# design.net
KiCad netlist of a schematic drawn in Altium Designer
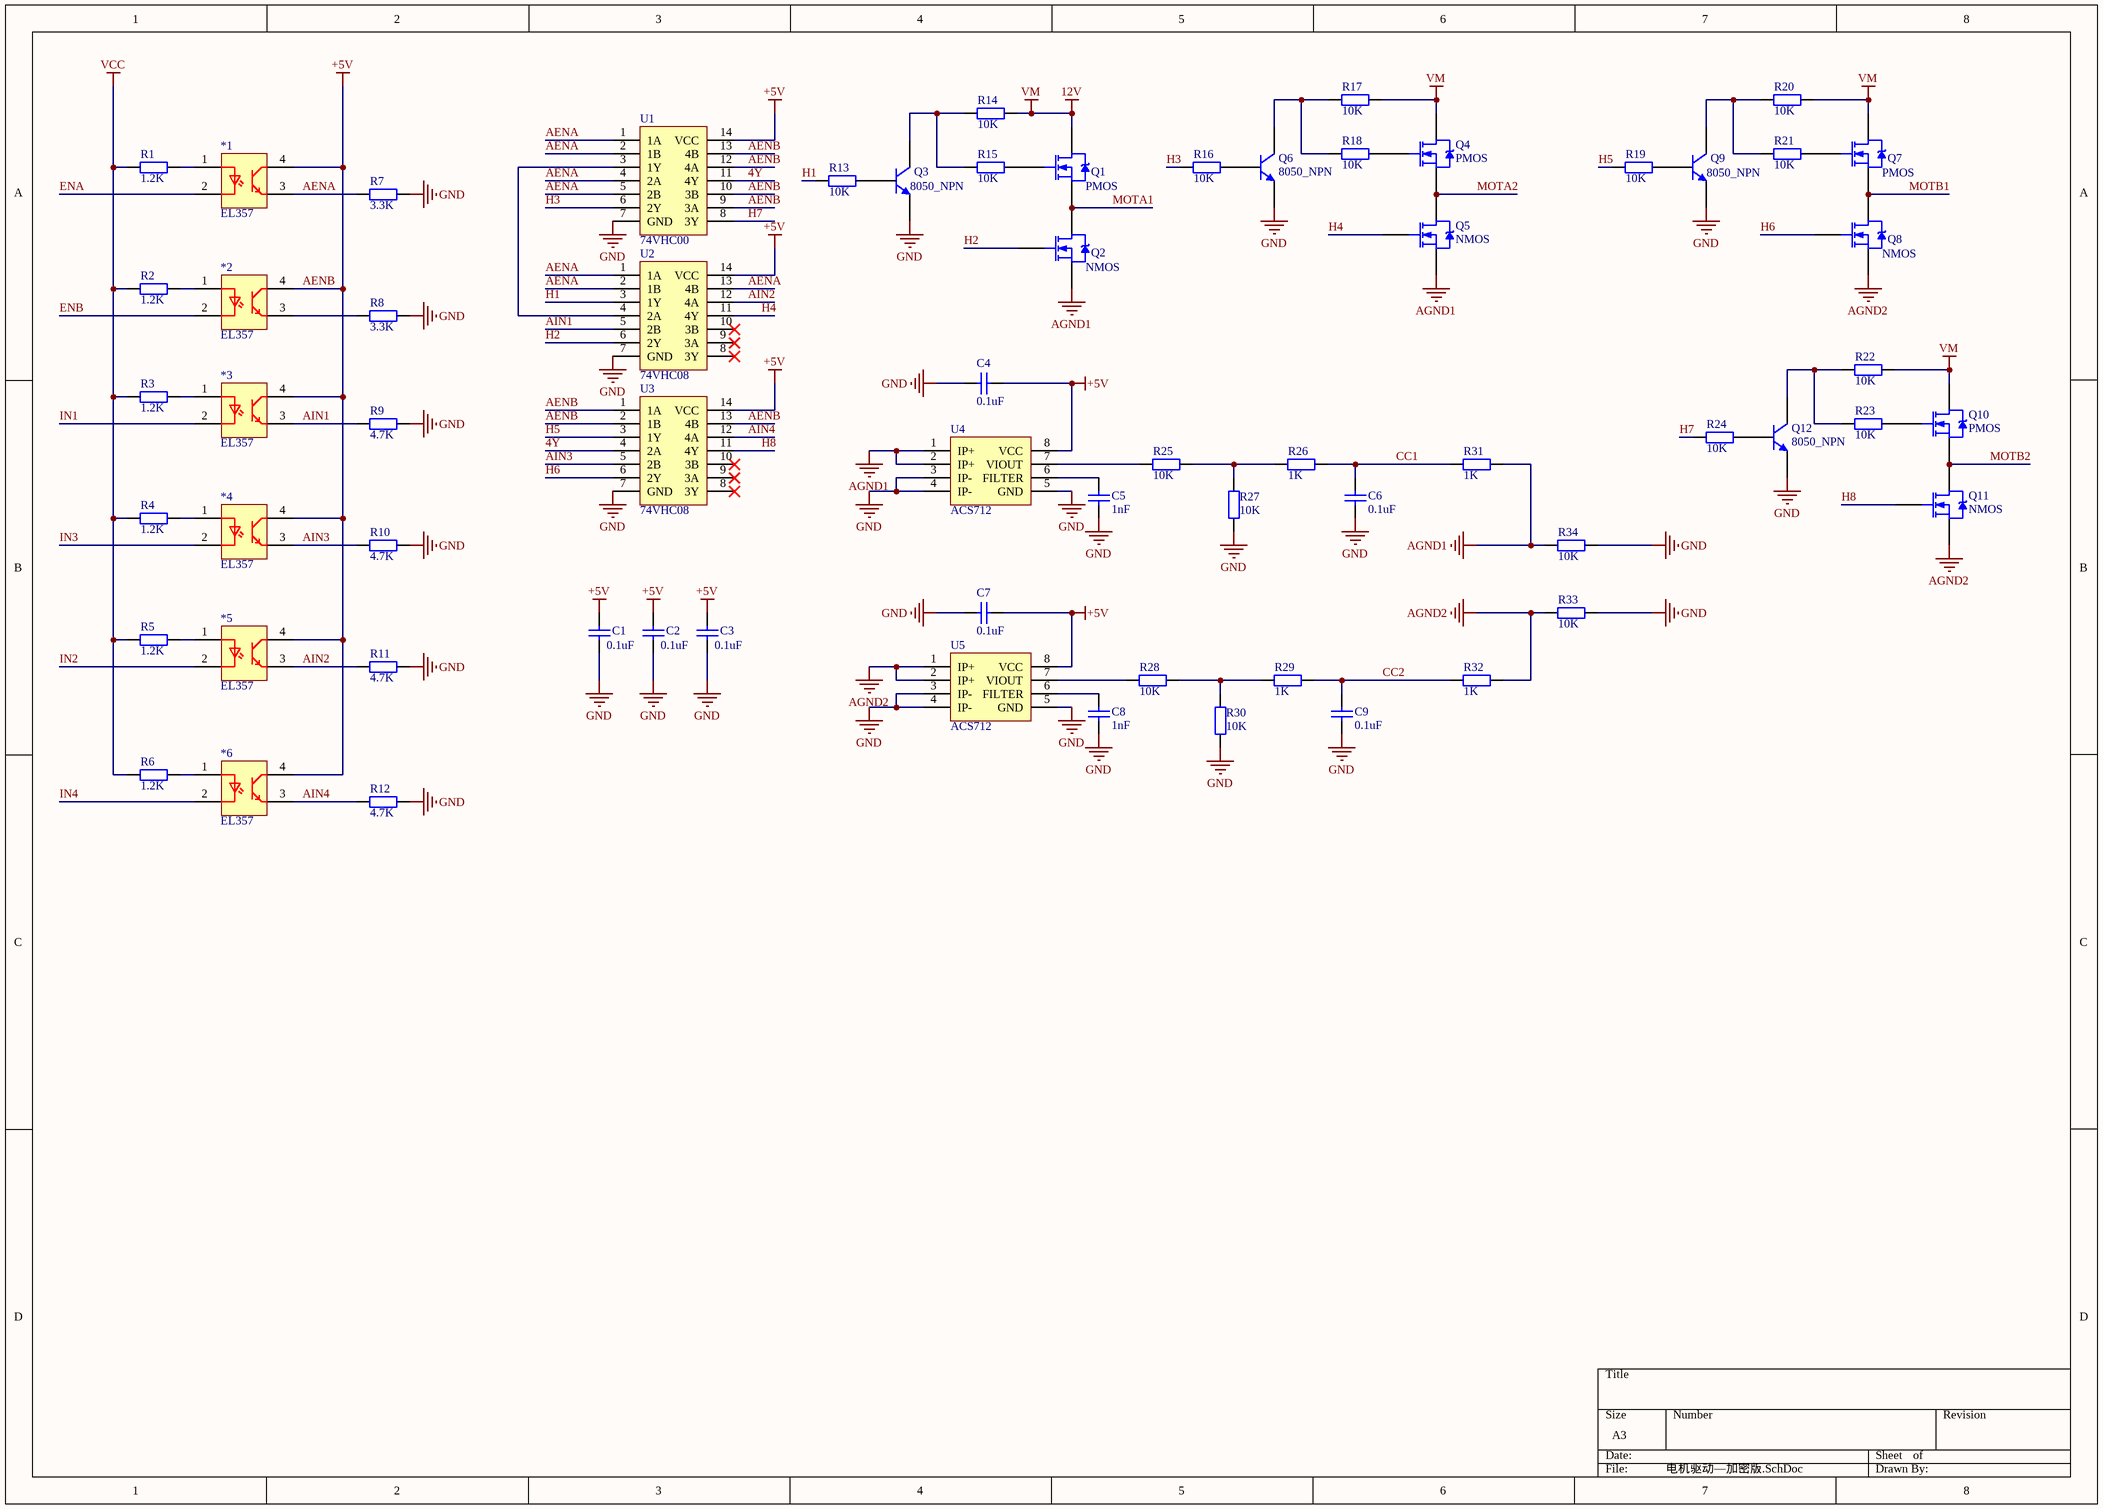
[diagram p0: 电机驱动—加密版.SchDoc]

(export (version "E")
  (design (tool "Eeschema 10.0.6"))
  (components
    (comp (ref "*1") (value "EL357") (footprint "EL357") (libsource (lib "EL357") (part "Component_1")))
    (comp (ref "*2") (value "EL357") (footprint "EL357") (libsource (lib "EL357") (part "Component_1")))
    (comp (ref "*3") (value "EL357") (footprint "EL357") (libsource (lib "EL357") (part "Component_1")))
    (comp (ref "*4") (value "EL357") (footprint "EL357") (libsource (lib "EL357") (part "Component_1")))
    (comp (ref "*5") (value "EL357") (footprint "EL357") (libsource (lib "EL357") (part "Component_1")))
    (comp (ref "*6") (value "EL357") (footprint "EL357") (libsource (lib "EL357") (part "Component_1")))
    (comp (ref "C1")
      (value "0.1uF")
      (footprint "1608[0603]")
      (description "Capacitor (Semiconductor SIM Model)")
      (fields (field (name "Comment") "104") (field (name "PUBLISHER") "Altium Limited"))
      (libsource (lib "Miscellaneous Devices") (part "Cap Semi"))
    )
    (comp (ref "C2")
      (value "0.1uF")
      (footprint "1608[0603]")
      (description "Capacitor (Semiconductor SIM Model)")
      (fields (field (name "Comment") "104") (field (name "PUBLISHER") "Altium Limited"))
      (libsource (lib "Miscellaneous Devices") (part "Cap Semi"))
    )
    (comp (ref "C3")
      (value "0.1uF")
      (footprint "1608[0603]")
      (description "Capacitor (Semiconductor SIM Model)")
      (fields (field (name "Comment") "104") (field (name "PUBLISHER") "Altium Limited"))
      (libsource (lib "Miscellaneous Devices") (part "Cap Semi"))
    )
    (comp (ref "C4")
      (value "0.1uF")
      (footprint "1608[0603]")
      (description "Capacitor (Semiconductor SIM Model)")
      (fields (field (name "Comment") "104") (field (name "PUBLISHER") "Altium Limited"))
      (libsource (lib "Miscellaneous Devices") (part "Cap Semi"))
    )
    (comp (ref "C5")
      (value "1nF")
      (footprint "1608[0603]")
      (description "Capacitor (Semiconductor SIM Model)")
      (fields (field (name "Comment") "102") (field (name "PUBLISHER") "Altium Limited"))
      (libsource (lib "Miscellaneous Devices") (part "Cap Semi"))
    )
    (comp (ref "C6")
      (value "0.1uF")
      (footprint "1608[0603]")
      (description "Capacitor (Semiconductor SIM Model)")
      (fields (field (name "Comment") "104") (field (name "PUBLISHER") "Altium Limited"))
      (libsource (lib "Miscellaneous Devices") (part "Cap Semi"))
    )
    (comp (ref "C7")
      (value "0.1uF")
      (footprint "1608[0603]")
      (description "Capacitor (Semiconductor SIM Model)")
      (fields (field (name "Comment") "104") (field (name "PUBLISHER") "Altium Limited"))
      (libsource (lib "Miscellaneous Devices") (part "Cap Semi"))
    )
    (comp (ref "C8")
      (value "1nF")
      (footprint "1608[0603]")
      (description "Capacitor (Semiconductor SIM Model)")
      (fields (field (name "Comment") "102") (field (name "PUBLISHER") "Altium Limited"))
      (libsource (lib "Miscellaneous Devices") (part "Cap Semi"))
    )
    (comp (ref "C9")
      (value "0.1uF")
      (footprint "1608[0603]")
      (description "Capacitor (Semiconductor SIM Model)")
      (fields (field (name "Comment") "104") (field (name "PUBLISHER") "Altium Limited"))
      (libsource (lib "Miscellaneous Devices") (part "Cap Semi"))
    )
    (comp (ref "Q1")
      (value "PMOS")
      (footprint "TO-252AA_M")
      (libsource (lib "Free Documents") (part "IRLR7843"))
    )
    (comp (ref "Q2")
      (value "NMOS")
      (footprint "TO-252AA_M")
      (libsource (lib "Free Documents") (part "IRLR7843"))
    )
    (comp (ref "Q3")
      (value "8050_NPN")
      (footprint "SOT-23")
      (description "NPN General Purpose Amplifier")
      (fields (field (name "PUBLISHER") "Altium Limited"))
      (libsource (lib "Miscellaneous Devices") (part "2N3904"))
    )
    (comp (ref "Q4")
      (value "PMOS")
      (footprint "TO-252AA_M")
      (libsource (lib "Free Documents") (part "IRLR7843"))
    )
    (comp (ref "Q5")
      (value "NMOS")
      (footprint "TO-252AA_M")
      (libsource (lib "Free Documents") (part "IRLR7843"))
    )
    (comp (ref "Q6")
      (value "8050_NPN")
      (footprint "SOT-23")
      (description "NPN General Purpose Amplifier")
      (fields (field (name "PUBLISHER") "Altium Limited"))
      (libsource (lib "Miscellaneous Devices") (part "2N3904"))
    )
    (comp (ref "Q7")
      (value "PMOS")
      (footprint "TO-252AA_M")
      (libsource (lib "Free Documents") (part "IRLR7843"))
    )
    (comp (ref "Q8")
      (value "NMOS")
      (footprint "TO-252AA_M")
      (libsource (lib "Free Documents") (part "IRLR7843"))
    )
    (comp (ref "Q9")
      (value "8050_NPN")
      (footprint "SOT-23")
      (description "NPN General Purpose Amplifier")
      (fields (field (name "PUBLISHER") "Altium Limited"))
      (libsource (lib "Miscellaneous Devices") (part "2N3904"))
    )
    (comp (ref "Q10")
      (value "PMOS")
      (footprint "TO-252AA_M")
      (libsource (lib "Free Documents") (part "IRLR7843"))
    )
    (comp (ref "Q11")
      (value "NMOS")
      (footprint "TO-252AA_M")
      (libsource (lib "Free Documents") (part "IRLR7843"))
    )
    (comp (ref "Q12")
      (value "8050_NPN")
      (footprint "SOT-23")
      (description "NPN General Purpose Amplifier")
      (fields (field (name "PUBLISHER") "Altium Limited"))
      (libsource (lib "Miscellaneous Devices") (part "2N3904"))
    )
    (comp (ref "R1") (value "1.2K") (footprint "0603-r") (libsource (lib "K60P144") (part "RES")))
    (comp (ref "R2") (value "1.2K") (footprint "0603-r") (libsource (lib "K60P144") (part "RES")))
    (comp (ref "R3") (value "1.2K") (footprint "0603-r") (libsource (lib "K60P144") (part "RES")))
    (comp (ref "R4") (value "1.2K") (footprint "0603-r") (libsource (lib "K60P144") (part "RES")))
    (comp (ref "R5") (value "1.2K") (footprint "0603-r") (libsource (lib "K60P144") (part "RES")))
    (comp (ref "R6") (value "1.2K") (footprint "0603-r") (libsource (lib "K60P144") (part "RES")))
    (comp (ref "R7") (value "3.3K") (footprint "0603-r") (libsource (lib "K60P144") (part "RES")))
    (comp (ref "R8") (value "3.3K") (footprint "0603-r") (libsource (lib "K60P144") (part "RES")))
    (comp (ref "R9") (value "4.7K") (footprint "0603-r") (libsource (lib "K60P144") (part "RES")))
    (comp (ref "R10") (value "4.7K") (footprint "0603-r") (libsource (lib "K60P144") (part "RES")))
    (comp (ref "R11") (value "4.7K") (footprint "0603-r") (libsource (lib "K60P144") (part "RES")))
    (comp (ref "R12") (value "4.7K") (footprint "0603-r") (libsource (lib "K60P144") (part "RES")))
    (comp (ref "R13") (value "10K") (footprint "0603-r") (libsource (lib "K60P144") (part "RES")))
    (comp (ref "R14") (value "10K") (footprint "0603-r") (libsource (lib "K60P144") (part "RES")))
    (comp (ref "R15") (value "10K") (footprint "0603-r") (libsource (lib "K60P144") (part "RES")))
    (comp (ref "R16") (value "10K") (footprint "0603-r") (libsource (lib "K60P144") (part "RES")))
    (comp (ref "R17") (value "10K") (footprint "0603-r") (libsource (lib "K60P144") (part "RES")))
    (comp (ref "R18") (value "10K") (footprint "0603-r") (libsource (lib "K60P144") (part "RES")))
    (comp (ref "R19") (value "10K") (footprint "0603-r") (libsource (lib "K60P144") (part "RES")))
    (comp (ref "R20") (value "10K") (footprint "0603-r") (libsource (lib "K60P144") (part "RES")))
    (comp (ref "R21") (value "10K") (footprint "0603-r") (libsource (lib "K60P144") (part "RES")))
    (comp (ref "R22") (value "10K") (footprint "0603-r") (libsource (lib "K60P144") (part "RES")))
    (comp (ref "R23") (value "10K") (footprint "0603-r") (libsource (lib "K60P144") (part "RES")))
    (comp (ref "R24") (value "10K") (footprint "0603-r") (libsource (lib "K60P144") (part "RES")))
    (comp (ref "R25") (value "10K") (footprint "0603-r") (libsource (lib "K60P144") (part "RES")))
    (comp (ref "R26") (value "1K") (footprint "0603-r") (libsource (lib "K60P144") (part "RES")))
    (comp (ref "R27") (value "10K") (footprint "0603-r") (libsource (lib "") (part "RES_1")))
    (comp (ref "R28") (value "10K") (footprint "0603-r") (libsource (lib "K60P144") (part "RES")))
    (comp (ref "R29") (value "1K") (footprint "0603-r") (libsource (lib "K60P144") (part "RES")))
    (comp (ref "R30") (value "10K") (footprint "0603-r") (libsource (lib "") (part "RES_1")))
    (comp (ref "R31") (value "1K") (footprint "0603-r") (libsource (lib "K60P144") (part "RES")))
    (comp (ref "R32") (value "1K") (footprint "0603-r") (libsource (lib "K60P144") (part "RES")))
    (comp (ref "R33") (value "10K") (footprint "0603-r") (libsource (lib "") (part "RES_2")))
    (comp (ref "R34") (value "10K") (footprint "0603-r") (libsource (lib "") (part "RES_2")))
    (comp (ref "U1") (value "74VHC00") (footprint "SO-14") (libsource (lib "74VHC00") (part "Component_1")))
    (comp (ref "U2") (value "74VHC08") (footprint "SO-14") (libsource (lib "74VHC00") (part "Component_1")))
    (comp (ref "U3") (value "74VHC08") (footprint "SO-14") (libsource (lib "74VHC00") (part "Component_1")))
    (comp (ref "U4") (value "ACS712") (footprint "SO-8") (libsource (lib "acs712") (part "Component_1")))
    (comp (ref "U5") (value "ACS712") (footprint "SO-8") (libsource (lib "acs712") (part "Component_1")))
  )
  (nets
    (net (code "1") (name "+5V") (class "Default")
      (node (ref "*1") (pin "4") (pinfunction "4_4") (pintype "passive"))
      (node (ref "*2") (pin "4") (pinfunction "4_4") (pintype "passive"))
      (node (ref "*3") (pin "4") (pinfunction "4_4") (pintype "passive"))
      (node (ref "*4") (pin "4") (pinfunction "4_4") (pintype "passive"))
      (node (ref "*5") (pin "4") (pinfunction "4_4") (pintype "passive"))
      (node (ref "*6") (pin "4") (pinfunction "4_4") (pintype "passive"))
      (node (ref "C1") (pin "2") (pinfunction "2_2") (pintype "passive"))
      (node (ref "C2") (pin "2") (pinfunction "2_2") (pintype "passive"))
      (node (ref "C3") (pin "2") (pinfunction "2_2") (pintype "passive"))
      (node (ref "C4") (pin "2") (pinfunction "2_2") (pintype "passive"))
      (node (ref "C7") (pin "2") (pinfunction "2_2") (pintype "passive"))
      (node (ref "U1") (pin "10") (pinfunction "3B_10") (pintype "passive"))
      (node (ref "U1") (pin "12") (pinfunction "4A_12") (pintype "passive"))
      (node (ref "U1") (pin "13") (pinfunction "4B_13") (pintype "passive"))
      (node (ref "U1") (pin "14") (pinfunction "VCC_14") (pintype "passive"))
      (node (ref "U1") (pin "9") (pinfunction "3A_9") (pintype "passive"))
      (node (ref "U2") (pin "14") (pinfunction "VCC_14") (pintype "passive"))
      (node (ref "U3") (pin "1") (pinfunction "1A_1") (pintype "passive"))
      (node (ref "U3") (pin "13") (pinfunction "4B_13") (pintype "passive"))
      (node (ref "U3") (pin "14") (pinfunction "VCC_14") (pintype "passive"))
      (node (ref "U3") (pin "2") (pinfunction "1B_2") (pintype "passive"))
      (node (ref "U4") (pin "8") (pinfunction "VCC_8") (pintype "passive"))
      (node (ref "U5") (pin "8") (pinfunction "VCC_8") (pintype "passive"))
    )
    (net (code "2") (name "/4Y") (class "Default")
      (node (ref "U1") (pin "11") (pinfunction "4Y_11") (pintype "passive"))
      (node (ref "U3") (pin "4") (pinfunction "2A_4") (pintype "passive"))
    )
    (net (code "3") (name "/AENA") (class "Default")
      (node (ref "*1") (pin "3") (pinfunction "3_3") (pintype "passive"))
      (node (ref "R7") (pin "1") (pinfunction "1_1") (pintype "passive"))
      (node (ref "U1") (pin "1") (pinfunction "1A_1") (pintype "passive"))
      (node (ref "U1") (pin "2") (pinfunction "1B_2") (pintype "passive"))
      (node (ref "U1") (pin "4") (pinfunction "2A_4") (pintype "passive"))
      (node (ref "U1") (pin "5") (pinfunction "2B_5") (pintype "passive"))
      (node (ref "U2") (pin "1") (pinfunction "1A_1") (pintype "passive"))
      (node (ref "U2") (pin "13") (pinfunction "4B_13") (pintype "passive"))
      (node (ref "U2") (pin "2") (pinfunction "1B_2") (pintype "passive"))
    )
    (net (code "4") (name "/AIN1") (class "Default")
      (node (ref "*3") (pin "3") (pinfunction "3_3") (pintype "passive"))
      (node (ref "R9") (pin "1") (pinfunction "1_1") (pintype "passive"))
      (node (ref "U2") (pin "5") (pinfunction "2B_5") (pintype "passive"))
    )
    (net (code "5") (name "/AIN2") (class "Default")
      (node (ref "*5") (pin "3") (pinfunction "3_3") (pintype "passive"))
      (node (ref "R11") (pin "1") (pinfunction "1_1") (pintype "passive"))
      (node (ref "U2") (pin "12") (pinfunction "4A_12") (pintype "passive"))
    )
    (net (code "6") (name "/AIN3") (class "Default")
      (node (ref "*4") (pin "3") (pinfunction "3_3") (pintype "passive"))
      (node (ref "R10") (pin "1") (pinfunction "1_1") (pintype "passive"))
      (node (ref "U3") (pin "5") (pinfunction "2B_5") (pintype "passive"))
    )
    (net (code "7") (name "/AIN4") (class "Default")
      (node (ref "*6") (pin "3") (pinfunction "3_3") (pintype "passive"))
      (node (ref "R12") (pin "1") (pinfunction "1_1") (pintype "passive"))
      (node (ref "U3") (pin "12") (pinfunction "4A_12") (pintype "passive"))
    )
    (net (code "8") (name "/CC1") (class "Default")
      (node (ref "C6") (pin "2") (pinfunction "2_2") (pintype "passive"))
      (node (ref "R26") (pin "2") (pinfunction "2_2") (pintype "passive"))
      (node (ref "R31") (pin "1") (pinfunction "1_1") (pintype "passive"))
    )
    (net (code "9") (name "/CC2") (class "Default")
      (node (ref "C9") (pin "2") (pinfunction "2_2") (pintype "passive"))
      (node (ref "R29") (pin "2") (pinfunction "2_2") (pintype "passive"))
      (node (ref "R32") (pin "1") (pinfunction "1_1") (pintype "passive"))
    )
    (net (code "10") (name "/ENA") (class "Default")
      (node (ref "*1") (pin "2") (pinfunction "2_2") (pintype "passive"))
    )
    (net (code "11") (name "/ENB") (class "Default")
      (node (ref "*2") (pin "2") (pinfunction "2_2") (pintype "passive"))
    )
    (net (code "12") (name "/H1") (class "Default")
      (node (ref "R13") (pin "1") (pinfunction "1_1") (pintype "passive"))
      (node (ref "U2") (pin "3") (pinfunction "1Y_3") (pintype "passive"))
    )
    (net (code "13") (name "/H2") (class "Default")
      (node (ref "Q2") (pin "1") (pinfunction "G_1") (pintype "passive"))
      (node (ref "U2") (pin "6") (pinfunction "2Y_6") (pintype "passive"))
    )
    (net (code "14") (name "/H3") (class "Default")
      (node (ref "R16") (pin "1") (pinfunction "1_1") (pintype "passive"))
      (node (ref "U1") (pin "6") (pinfunction "2Y_6") (pintype "passive"))
    )
    (net (code "15") (name "/H4") (class "Default")
      (node (ref "Q5") (pin "1") (pinfunction "G_1") (pintype "passive"))
      (node (ref "U2") (pin "11") (pinfunction "4Y_11") (pintype "passive"))
    )
    (net (code "16") (name "/H5") (class "Default")
      (node (ref "R19") (pin "1") (pinfunction "1_1") (pintype "passive"))
      (node (ref "U3") (pin "3") (pinfunction "1Y_3") (pintype "passive"))
    )
    (net (code "17") (name "/H6") (class "Default")
      (node (ref "Q8") (pin "1") (pinfunction "G_1") (pintype "passive"))
      (node (ref "U3") (pin "6") (pinfunction "2Y_6") (pintype "passive"))
    )
    (net (code "18") (name "/H7") (class "Default")
      (node (ref "R24") (pin "1") (pinfunction "1_1") (pintype "passive"))
      (node (ref "U1") (pin "8") (pinfunction "3Y_8") (pintype "passive"))
    )
    (net (code "19") (name "/H8") (class "Default")
      (node (ref "Q11") (pin "1") (pinfunction "G_1") (pintype "passive"))
      (node (ref "U3") (pin "11") (pinfunction "4Y_11") (pintype "passive"))
    )
    (net (code "20") (name "/IN1") (class "Default")
      (node (ref "*3") (pin "2") (pinfunction "2_2") (pintype "passive"))
    )
    (net (code "21") (name "/IN2") (class "Default")
      (node (ref "*5") (pin "2") (pinfunction "2_2") (pintype "passive"))
    )
    (net (code "22") (name "/IN3") (class "Default")
      (node (ref "*4") (pin "2") (pinfunction "2_2") (pintype "passive"))
    )
    (net (code "23") (name "/IN4") (class "Default")
      (node (ref "*6") (pin "2") (pinfunction "2_2") (pintype "passive"))
    )
    (net (code "24") (name "/MOTA1") (class "Default")
      (node (ref "Q1") (pin "3") (pinfunction "S_3") (pintype "passive"))
      (node (ref "Q2") (pin "4") (pinfunction "D_4") (pintype "passive"))
    )
    (net (code "25") (name "/MOTA2") (class "Default")
      (node (ref "Q4") (pin "3") (pinfunction "S_3") (pintype "passive"))
      (node (ref "Q5") (pin "4") (pinfunction "D_4") (pintype "passive"))
    )
    (net (code "26") (name "/MOTB1") (class "Default")
      (node (ref "Q7") (pin "3") (pinfunction "S_3") (pintype "passive"))
      (node (ref "Q8") (pin "4") (pinfunction "D_4") (pintype "passive"))
    )
    (net (code "27") (name "/MOTB2") (class "Default")
      (node (ref "Q10") (pin "3") (pinfunction "S_3") (pintype "passive"))
      (node (ref "Q11") (pin "4") (pinfunction "D_4") (pintype "passive"))
    )
    (net (code "28") (name "12V") (class "Default")
      (node (ref "Q1") (pin "4") (pinfunction "D_4") (pintype "passive"))
      (node (ref "Q10") (pin "4") (pinfunction "D_4") (pintype "passive"))
      (node (ref "Q4") (pin "4") (pinfunction "D_4") (pintype "passive"))
      (node (ref "Q7") (pin "4") (pinfunction "D_4") (pintype "passive"))
      (node (ref "R14") (pin "2") (pinfunction "2_2") (pintype "passive"))
      (node (ref "R17") (pin "2") (pinfunction "2_2") (pintype "passive"))
      (node (ref "R20") (pin "2") (pinfunction "2_2") (pintype "passive"))
      (node (ref "R22") (pin "2") (pinfunction "2_2") (pintype "passive"))
    )
    (net (code "29") (name "AGND1") (class "Default")
      (node (ref "Q2") (pin "3") (pinfunction "S_3") (pintype "passive"))
      (node (ref "Q5") (pin "3") (pinfunction "S_3") (pintype "passive"))
      (node (ref "R31") (pin "2") (pinfunction "2_2") (pintype "passive"))
      (node (ref "R34") (pin "2") (pinfunction "2_2") (pintype "passive"))
      (node (ref "U4") (pin "1") (pinfunction "IP+_1") (pintype "passive"))
      (node (ref "U4") (pin "2") (pinfunction "IP+_2") (pintype "passive"))
    )
    (net (code "30") (name "AGND2") (class "Default")
      (node (ref "Q11") (pin "3") (pinfunction "S_3") (pintype "passive"))
      (node (ref "Q8") (pin "3") (pinfunction "S_3") (pintype "passive"))
      (node (ref "R32") (pin "2") (pinfunction "2_2") (pintype "passive"))
      (node (ref "R33") (pin "2") (pinfunction "2_2") (pintype "passive"))
      (node (ref "U5") (pin "1") (pinfunction "IP+_1") (pintype "passive"))
      (node (ref "U5") (pin "2") (pinfunction "IP+_2") (pintype "passive"))
    )
    (net (code "31") (name "GND") (class "Default")
      (node (ref "C1") (pin "1") (pinfunction "1_1") (pintype "passive"))
      (node (ref "C2") (pin "1") (pinfunction "1_1") (pintype "passive"))
      (node (ref "C3") (pin "1") (pinfunction "1_1") (pintype "passive"))
      (node (ref "C4") (pin "1") (pinfunction "1_1") (pintype "passive"))
      (node (ref "C5") (pin "1") (pinfunction "1_1") (pintype "passive"))
      (node (ref "C6") (pin "1") (pinfunction "1_1") (pintype "passive"))
      (node (ref "C7") (pin "1") (pinfunction "1_1") (pintype "passive"))
      (node (ref "C8") (pin "1") (pinfunction "1_1") (pintype "passive"))
      (node (ref "C9") (pin "1") (pinfunction "1_1") (pintype "passive"))
      (node (ref "Q12") (pin "1") (pinfunction "E_1") (pintype "passive"))
      (node (ref "Q3") (pin "1") (pinfunction "E_1") (pintype "passive"))
      (node (ref "Q6") (pin "1") (pinfunction "E_1") (pintype "passive"))
      (node (ref "Q9") (pin "1") (pinfunction "E_1") (pintype "passive"))
      (node (ref "R10") (pin "2") (pinfunction "2_2") (pintype "passive"))
      (node (ref "R11") (pin "2") (pinfunction "2_2") (pintype "passive"))
      (node (ref "R12") (pin "2") (pinfunction "2_2") (pintype "passive"))
      (node (ref "R27") (pin "1") (pinfunction "1_1") (pintype "passive"))
      (node (ref "R30") (pin "1") (pinfunction "1_1") (pintype "passive"))
      (node (ref "R33") (pin "1") (pinfunction "1_1") (pintype "passive"))
      (node (ref "R34") (pin "1") (pinfunction "1_1") (pintype "passive"))
      (node (ref "R7") (pin "2") (pinfunction "2_2") (pintype "passive"))
      (node (ref "R8") (pin "2") (pinfunction "2_2") (pintype "passive"))
      (node (ref "R9") (pin "2") (pinfunction "2_2") (pintype "passive"))
      (node (ref "U1") (pin "7") (pinfunction "GND_7") (pintype "passive"))
      (node (ref "U2") (pin "7") (pinfunction "GND_7") (pintype "passive"))
      (node (ref "U3") (pin "7") (pinfunction "GND_7") (pintype "passive"))
      (node (ref "U4") (pin "3") (pinfunction "IP-_3") (pintype "passive"))
      (node (ref "U4") (pin "4") (pinfunction "IP-_4") (pintype "passive"))
      (node (ref "U4") (pin "5") (pinfunction "GND_5") (pintype "passive"))
      (node (ref "U5") (pin "3") (pinfunction "IP-_3") (pintype "passive"))
      (node (ref "U5") (pin "4") (pinfunction "IP-_4") (pintype "passive"))
      (node (ref "U5") (pin "5") (pinfunction "GND_5") (pintype "passive"))
    )
    (net (code "32") (name "Net-(*1-Pad1)") (class "Default")
      (node (ref "*1") (pin "1") (pinfunction "1_1") (pintype "passive"))
      (node (ref "R1") (pin "2") (pinfunction "2_2") (pintype "passive"))
    )
    (net (code "33") (name "Net-(*2-Pad1)") (class "Default")
      (node (ref "*2") (pin "1") (pinfunction "1_1") (pintype "passive"))
      (node (ref "R2") (pin "2") (pinfunction "2_2") (pintype "passive"))
    )
    (net (code "34") (name "Net-(*2-Pad3)") (class "Default")
      (node (ref "*2") (pin "3") (pinfunction "3_3") (pintype "passive"))
      (node (ref "R8") (pin "1") (pinfunction "1_1") (pintype "passive"))
    )
    (net (code "35") (name "Net-(*3-Pad1)") (class "Default")
      (node (ref "*3") (pin "1") (pinfunction "1_1") (pintype "passive"))
      (node (ref "R3") (pin "2") (pinfunction "2_2") (pintype "passive"))
    )
    (net (code "36") (name "Net-(*4-Pad1)") (class "Default")
      (node (ref "*4") (pin "1") (pinfunction "1_1") (pintype "passive"))
      (node (ref "R4") (pin "2") (pinfunction "2_2") (pintype "passive"))
    )
    (net (code "37") (name "Net-(*5-Pad1)") (class "Default")
      (node (ref "*5") (pin "1") (pinfunction "1_1") (pintype "passive"))
      (node (ref "R5") (pin "2") (pinfunction "2_2") (pintype "passive"))
    )
    (net (code "38") (name "Net-(*6-Pad1)") (class "Default")
      (node (ref "*6") (pin "1") (pinfunction "1_1") (pintype "passive"))
      (node (ref "R6") (pin "2") (pinfunction "2_2") (pintype "passive"))
    )
    (net (code "39") (name "Net-(Q1-G)") (class "Default")
      (node (ref "Q1") (pin "1") (pinfunction "G_1") (pintype "passive"))
      (node (ref "R15") (pin "2") (pinfunction "2_2") (pintype "passive"))
    )
    (net (code "40") (name "Net-(Q3-B)") (class "Default")
      (node (ref "Q3") (pin "2") (pinfunction "B_2") (pintype "passive"))
      (node (ref "R13") (pin "2") (pinfunction "2_2") (pintype "passive"))
    )
    (net (code "41") (name "Net-(Q3-C)") (class "Default")
      (node (ref "Q3") (pin "3") (pinfunction "C_3") (pintype "passive"))
      (node (ref "R14") (pin "1") (pinfunction "1_1") (pintype "passive"))
      (node (ref "R15") (pin "1") (pinfunction "1_1") (pintype "passive"))
    )
    (net (code "42") (name "Net-(Q4-G)") (class "Default")
      (node (ref "Q4") (pin "1") (pinfunction "G_1") (pintype "passive"))
      (node (ref "R18") (pin "2") (pinfunction "2_2") (pintype "passive"))
    )
    (net (code "43") (name "Net-(Q6-B)") (class "Default")
      (node (ref "Q6") (pin "2") (pinfunction "B_2") (pintype "passive"))
      (node (ref "R16") (pin "2") (pinfunction "2_2") (pintype "passive"))
    )
    (net (code "44") (name "Net-(Q6-C)") (class "Default")
      (node (ref "Q6") (pin "3") (pinfunction "C_3") (pintype "passive"))
      (node (ref "R17") (pin "1") (pinfunction "1_1") (pintype "passive"))
      (node (ref "R18") (pin "1") (pinfunction "1_1") (pintype "passive"))
    )
    (net (code "45") (name "Net-(Q7-G)") (class "Default")
      (node (ref "Q7") (pin "1") (pinfunction "G_1") (pintype "passive"))
      (node (ref "R21") (pin "2") (pinfunction "2_2") (pintype "passive"))
    )
    (net (code "46") (name "Net-(Q9-B)") (class "Default")
      (node (ref "Q9") (pin "2") (pinfunction "B_2") (pintype "passive"))
      (node (ref "R19") (pin "2") (pinfunction "2_2") (pintype "passive"))
    )
    (net (code "47") (name "Net-(Q9-C)") (class "Default")
      (node (ref "Q9") (pin "3") (pinfunction "C_3") (pintype "passive"))
      (node (ref "R20") (pin "1") (pinfunction "1_1") (pintype "passive"))
      (node (ref "R21") (pin "1") (pinfunction "1_1") (pintype "passive"))
    )
    (net (code "48") (name "Net-(Q10-G)") (class "Default")
      (node (ref "Q10") (pin "1") (pinfunction "G_1") (pintype "passive"))
      (node (ref "R23") (pin "2") (pinfunction "2_2") (pintype "passive"))
    )
    (net (code "49") (name "Net-(Q12-B)") (class "Default")
      (node (ref "Q12") (pin "2") (pinfunction "B_2") (pintype "passive"))
      (node (ref "R24") (pin "2") (pinfunction "2_2") (pintype "passive"))
    )
    (net (code "50") (name "Net-(Q12-C)") (class "Default")
      (node (ref "Q12") (pin "3") (pinfunction "C_3") (pintype "passive"))
      (node (ref "R22") (pin "1") (pinfunction "1_1") (pintype "passive"))
      (node (ref "R23") (pin "1") (pinfunction "1_1") (pintype "passive"))
    )
    (net (code "51") (name "Net-(R25-Pad2)") (class "Default")
      (node (ref "R25") (pin "2") (pinfunction "2_2") (pintype "passive"))
      (node (ref "R26") (pin "1") (pinfunction "1_1") (pintype "passive"))
      (node (ref "R27") (pin "2") (pinfunction "2_2") (pintype "passive"))
    )
    (net (code "52") (name "Net-(R28-Pad2)") (class "Default")
      (node (ref "R28") (pin "2") (pinfunction "2_2") (pintype "passive"))
      (node (ref "R29") (pin "1") (pinfunction "1_1") (pintype "passive"))
      (node (ref "R30") (pin "2") (pinfunction "2_2") (pintype "passive"))
    )
    (net (code "53") (name "Net-(U1-1Y)") (class "Default")
      (node (ref "U1") (pin "3") (pinfunction "1Y_3") (pintype "passive"))
      (node (ref "U2") (pin "4") (pinfunction "2A_4") (pintype "passive"))
    )
    (net (code "54") (name "Net-(U4-FILTER)") (class "Default")
      (node (ref "C5") (pin "2") (pinfunction "2_2") (pintype "passive"))
      (node (ref "U4") (pin "6") (pinfunction "FILTER_6") (pintype "passive"))
    )
    (net (code "55") (name "Net-(U4-VIOUT)") (class "Default")
      (node (ref "R25") (pin "1") (pinfunction "1_1") (pintype "passive"))
      (node (ref "U4") (pin "7") (pinfunction "VIOUT_7") (pintype "passive"))
    )
    (net (code "56") (name "Net-(U5-FILTER)") (class "Default")
      (node (ref "C8") (pin "2") (pinfunction "2_2") (pintype "passive"))
      (node (ref "U5") (pin "6") (pinfunction "FILTER_6") (pintype "passive"))
    )
    (net (code "57") (name "Net-(U5-VIOUT)") (class "Default")
      (node (ref "R28") (pin "1") (pinfunction "1_1") (pintype "passive"))
      (node (ref "U5") (pin "7") (pinfunction "VIOUT_7") (pintype "passive"))
    )
    (net (code "58") (name "VCC") (class "Default")
      (node (ref "R1") (pin "1") (pinfunction "1_1") (pintype "passive"))
      (node (ref "R2") (pin "1") (pinfunction "1_1") (pintype "passive"))
      (node (ref "R3") (pin "1") (pinfunction "1_1") (pintype "passive"))
      (node (ref "R4") (pin "1") (pinfunction "1_1") (pintype "passive"))
      (node (ref "R5") (pin "1") (pinfunction "1_1") (pintype "passive"))
      (node (ref "R6") (pin "1") (pinfunction "1_1") (pintype "passive"))
    )
    (net (code "59") (name "unconnected-(U2-3A-Pad9)") (class "Default")
      (node (ref "U2") (pin "9") (pinfunction "3A_9") (pintype "passive+no_connect"))
    )
    (net (code "60") (name "unconnected-(U2-3B-Pad10)") (class "Default")
      (node (ref "U2") (pin "10") (pinfunction "3B_10") (pintype "passive+no_connect"))
    )
    (net (code "61") (name "unconnected-(U2-3Y-Pad8)") (class "Default")
      (node (ref "U2") (pin "8") (pinfunction "3Y_8") (pintype "passive+no_connect"))
    )
    (net (code "62") (name "unconnected-(U3-3A-Pad9)") (class "Default")
      (node (ref "U3") (pin "9") (pinfunction "3A_9") (pintype "passive+no_connect"))
    )
    (net (code "63") (name "unconnected-(U3-3B-Pad10)") (class "Default")
      (node (ref "U3") (pin "10") (pinfunction "3B_10") (pintype "passive+no_connect"))
    )
    (net (code "64") (name "unconnected-(U3-3Y-Pad8)") (class "Default")
      (node (ref "U3") (pin "8") (pinfunction "3Y_8") (pintype "passive+no_connect"))
    )
  )
)
